# JammerCon_v1_1.net
KiCad netlist of a schematic drawn in Altium Designer
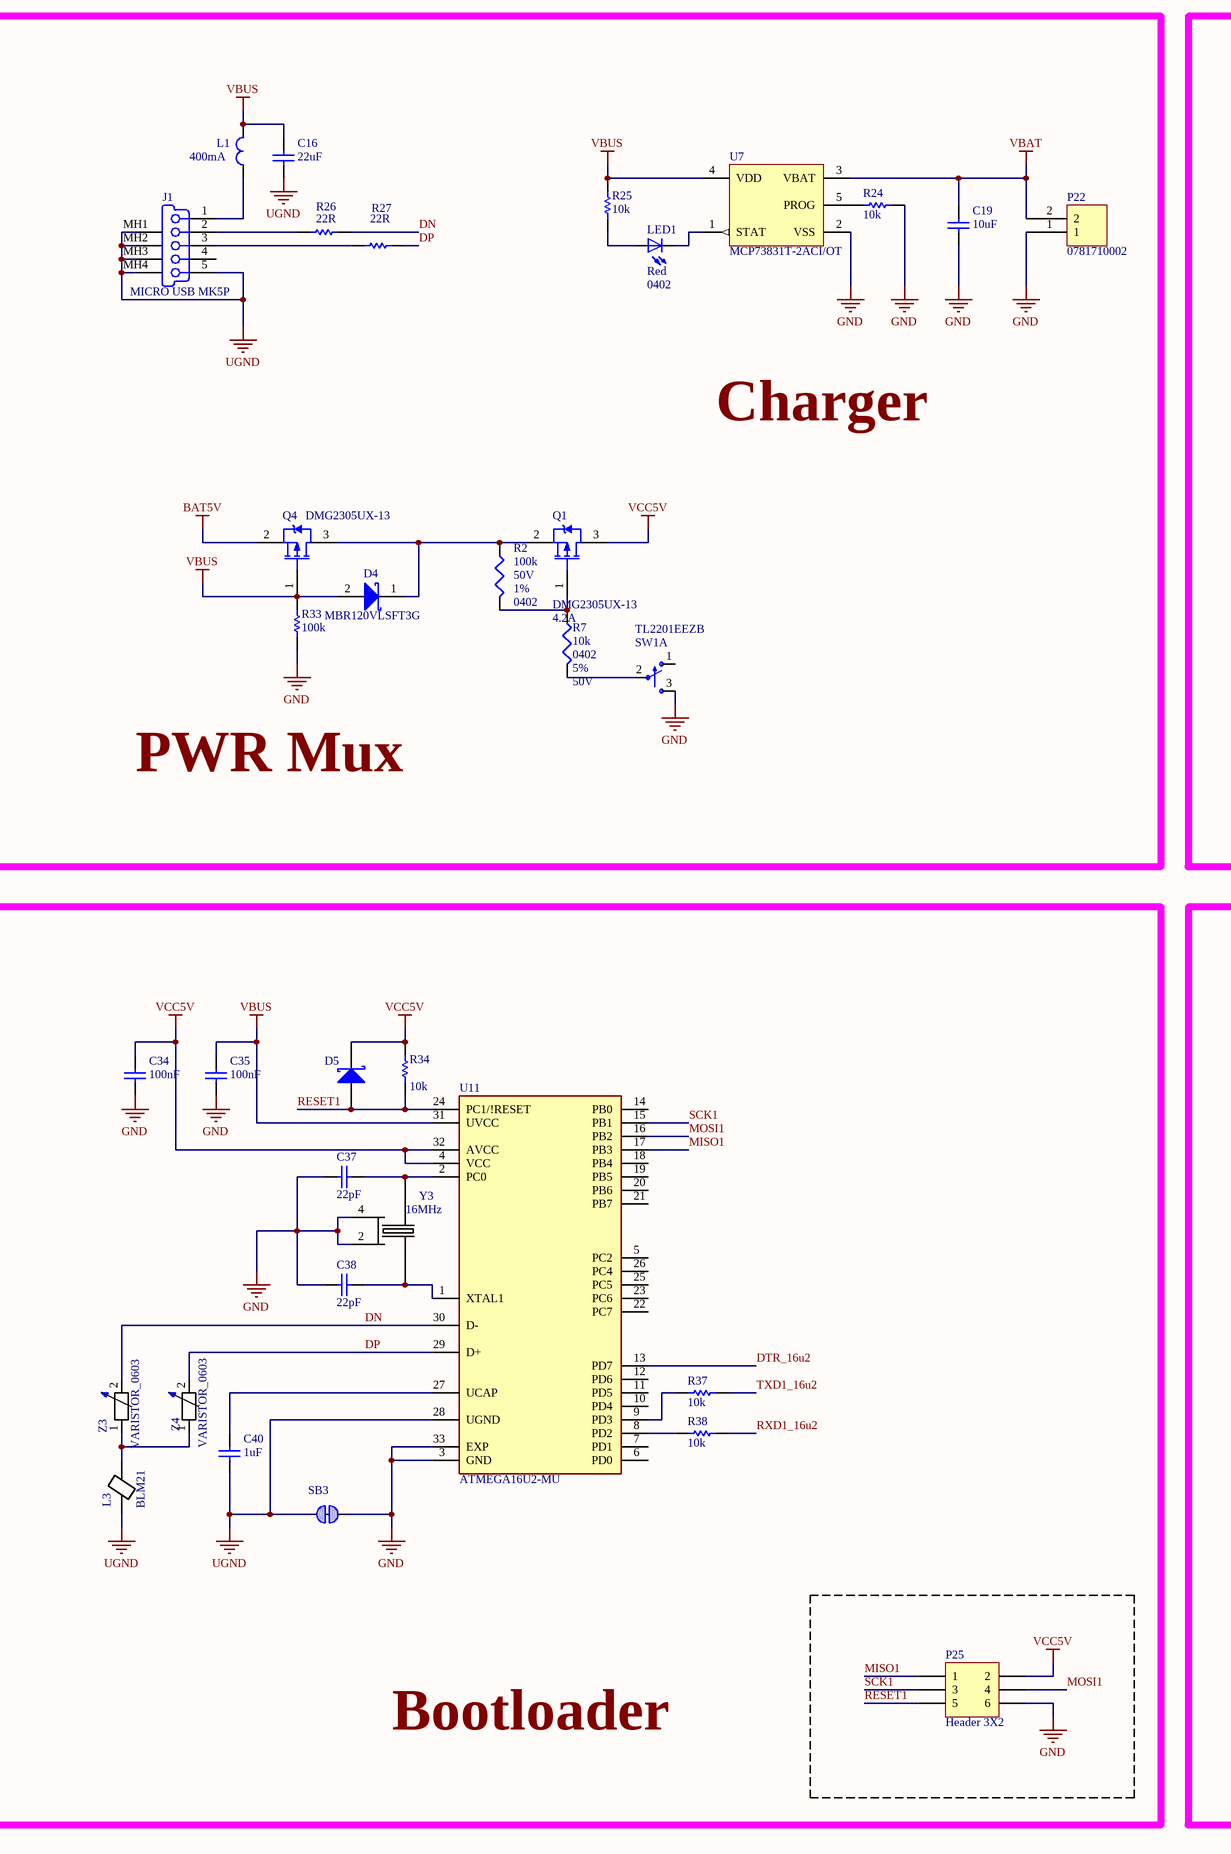
[diagram p0: JammerCon_v1.1.SchDoc, left]
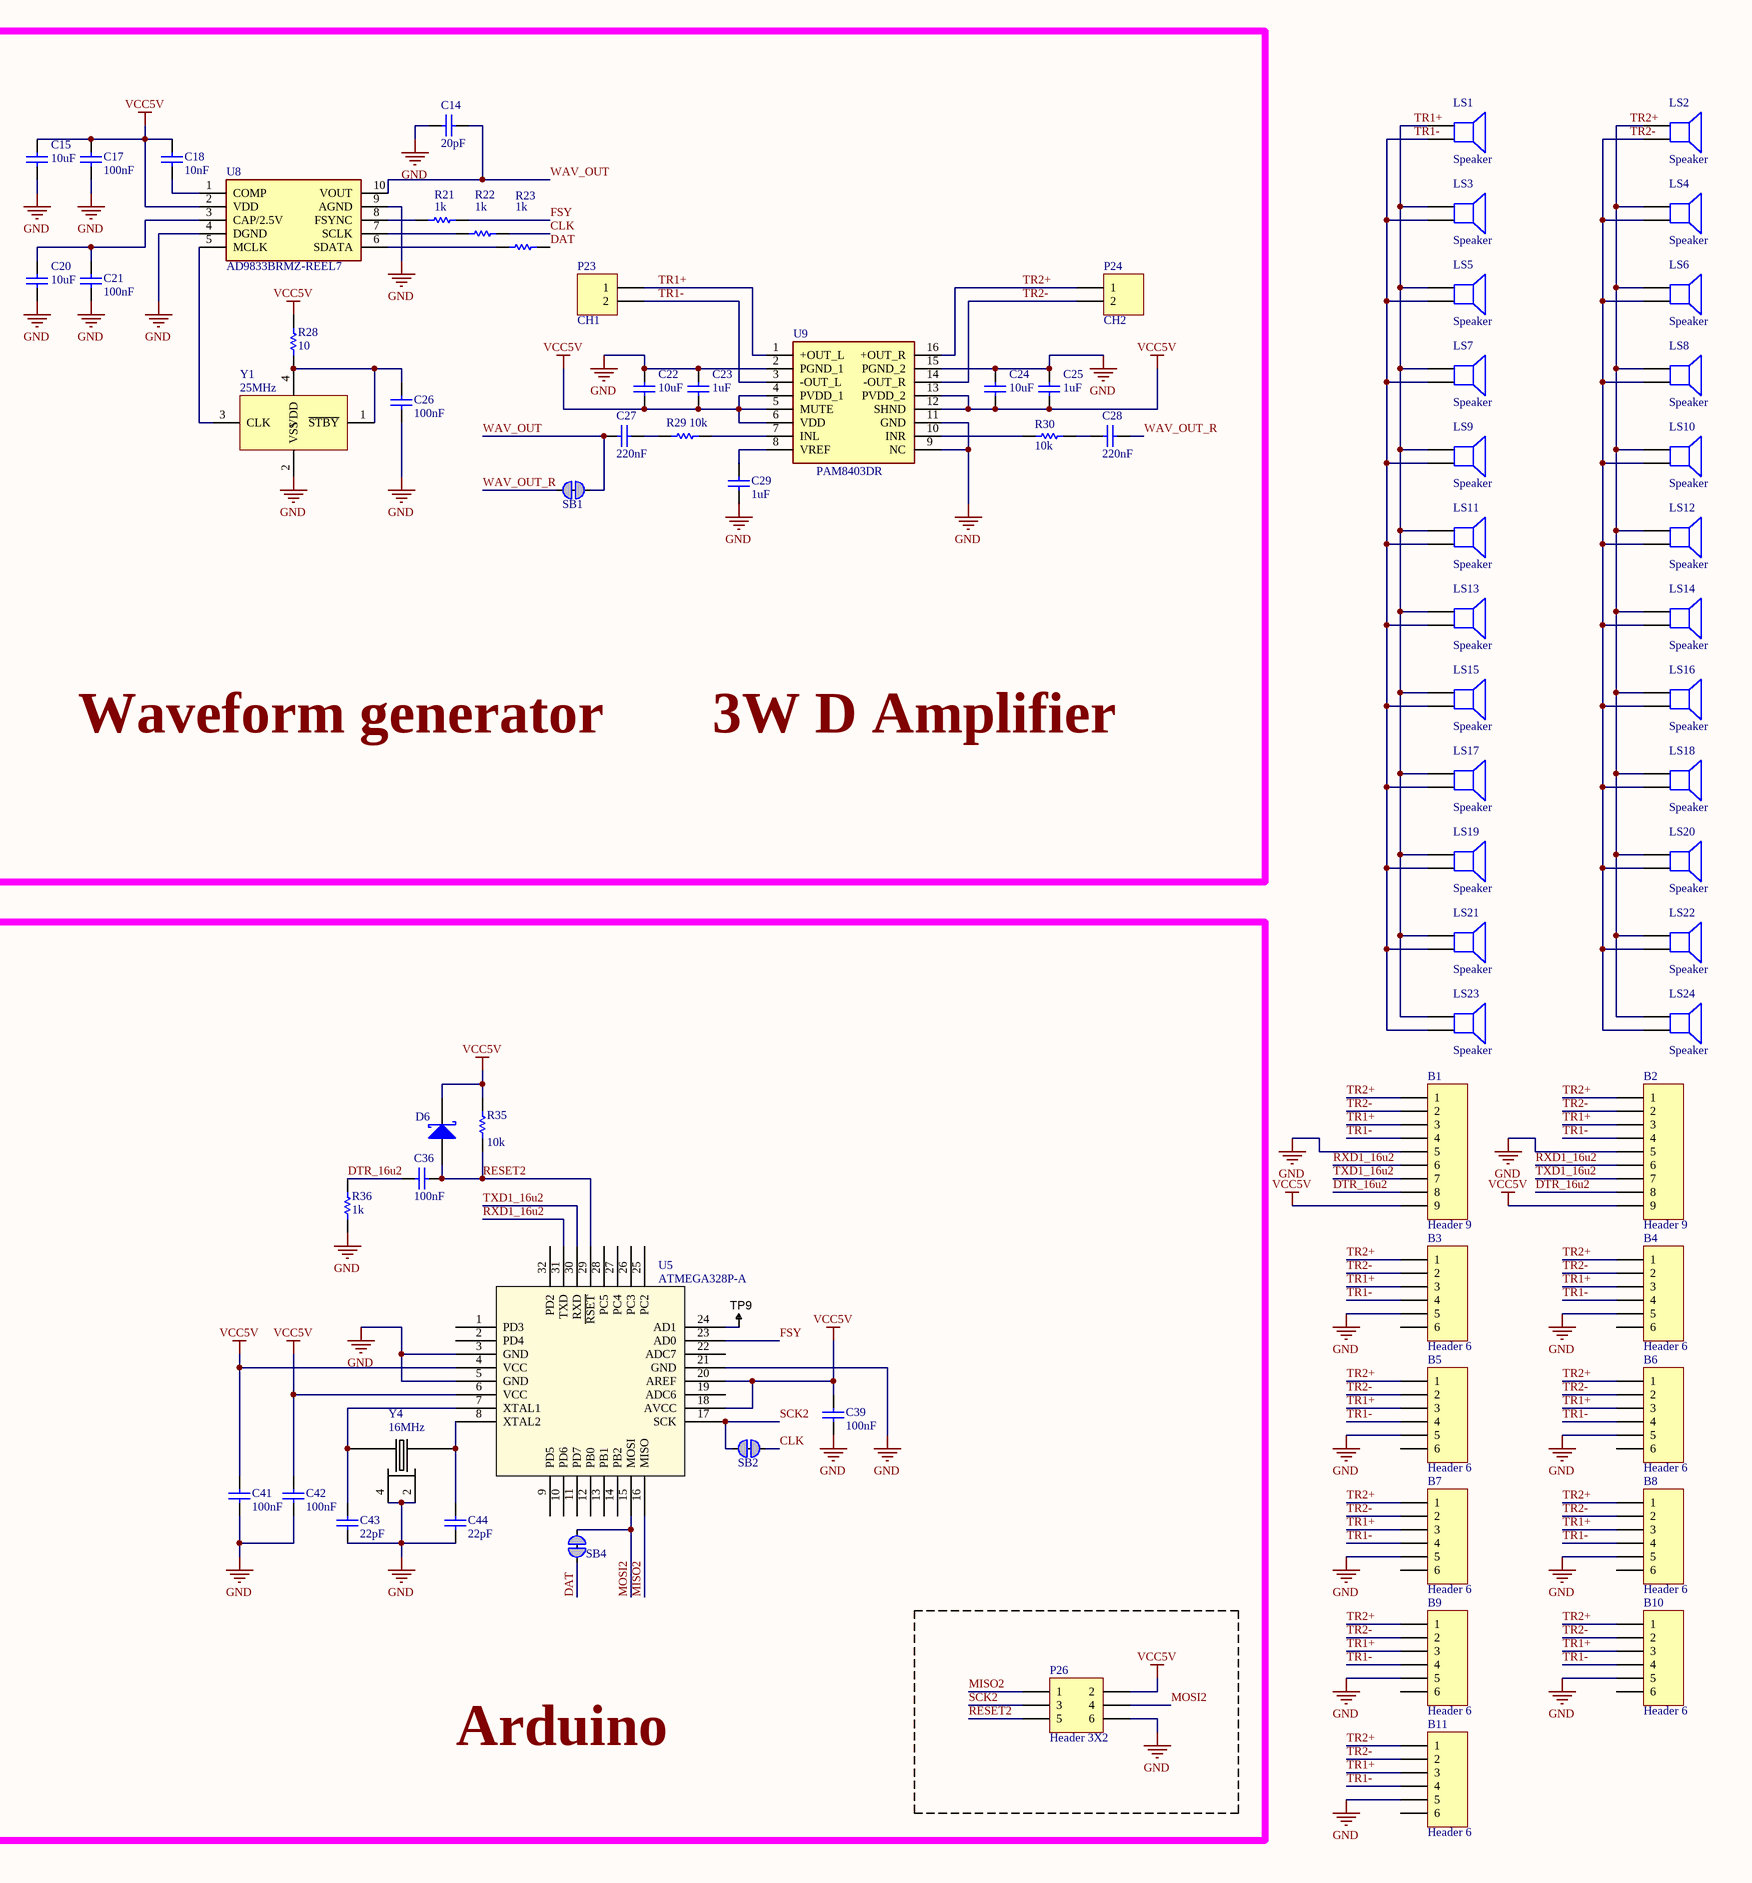
[diagram p1: JammerCon_v1.1.SchDoc, right]

(export (version "E")
  (design (tool "Eeschema 10.0.6"))
  (components
    (comp (ref "B1")
      (value "Header 9")
      (footprint "HDR1X9")
      (description "Header, 9-Pin")
      (fields (field (name "PUBLISHER") "Altium Limited"))
      (libsource (lib "Miscellaneous Connectors") (part "Header 9"))
    )
    (comp (ref "B2")
      (value "Header 9")
      (footprint "HDR1X9")
      (description "Header, 9-Pin")
      (fields (field (name "PUBLISHER") "Altium Limited"))
      (libsource (lib "Miscellaneous Connectors") (part "Header 9"))
    )
    (comp (ref "B3")
      (value "Header 6")
      (footprint "HDR1X6")
      (description "Header, 6-Pin")
      (fields (field (name "PUBLISHER") "Altium Limited"))
      (libsource (lib "Miscellaneous Connectors") (part "Header 6"))
    )
    (comp (ref "B4")
      (value "Header 6")
      (footprint "HDR1X6")
      (description "Header, 6-Pin")
      (fields (field (name "PUBLISHER") "Altium Limited"))
      (libsource (lib "Miscellaneous Connectors") (part "Header 6"))
    )
    (comp (ref "B5")
      (value "Header 6")
      (footprint "HDR1X6")
      (description "Header, 6-Pin")
      (fields (field (name "PUBLISHER") "Altium Limited"))
      (libsource (lib "Miscellaneous Connectors") (part "Header 6"))
    )
    (comp (ref "B6")
      (value "Header 6")
      (footprint "HDR1X6")
      (description "Header, 6-Pin")
      (fields (field (name "PUBLISHER") "Altium Limited"))
      (libsource (lib "Miscellaneous Connectors") (part "Header 6"))
    )
    (comp (ref "B7")
      (value "Header 6")
      (footprint "HDR1X6")
      (description "Header, 6-Pin")
      (fields (field (name "PUBLISHER") "Altium Limited"))
      (libsource (lib "Miscellaneous Connectors") (part "Header 6"))
    )
    (comp (ref "B8")
      (value "Header 6")
      (footprint "HDR1X6")
      (description "Header, 6-Pin")
      (fields (field (name "PUBLISHER") "Altium Limited"))
      (libsource (lib "Miscellaneous Connectors") (part "Header 6"))
    )
    (comp (ref "B9")
      (value "Header 6")
      (footprint "HDR1X6")
      (description "Header, 6-Pin")
      (fields (field (name "PUBLISHER") "Altium Limited"))
      (libsource (lib "Miscellaneous Connectors") (part "Header 6"))
    )
    (comp (ref "B10")
      (value "Header 6")
      (footprint "HDR1X6")
      (description "Header, 6-Pin")
      (fields (field (name "PUBLISHER") "Altium Limited"))
      (libsource (lib "Miscellaneous Connectors") (part "Header 6"))
    )
    (comp (ref "B11")
      (value "Header 6")
      (footprint "HDR1X6")
      (description "Header, 6-Pin")
      (fields (field (name "PUBLISHER") "Altium Limited"))
      (libsource (lib "Miscellaneous Connectors") (part "Header 6"))
    )
    (comp (ref "C14")
      (value "20pF")
      (footprint "C0402")
      (description "Capacitor (Semiconductor SIM Model)")
      (fields (field (name "Comment") "Cap Semi"))
      (libsource (lib "Miscellaneous Devices") (part "Cap Semi"))
    )
    (comp (ref "C15")
      (value "10uF")
      (footprint "C0805")
      (description "Capacitor (Semiconductor SIM Model)")
      (fields (field (name "Comment") "Cap Semi"))
      (libsource (lib "Miscellaneous Devices") (part "Cap Semi"))
    )
    (comp (ref "C16")
      (value "22uF")
      (footprint "C0603")
      (description "Capacitor (Semiconductor SIM Model)")
      (fields (field (name "Comment") "Cap Semi"))
      (libsource (lib "Miscellaneous Devices") (part "Cap Semi"))
    )
    (comp (ref "C17")
      (value "100nF")
      (footprint "R0402")
      (description "Capacitor (Semiconductor SIM Model)")
      (fields (field (name "Comment") "Cap Semi"))
      (libsource (lib "Miscellaneous Devices") (part "Cap Semi"))
    )
    (comp (ref "C18")
      (value "10nF")
      (footprint "R0402")
      (description "Capacitor (Semiconductor SIM Model)")
      (fields (field (name "Comment") "Cap Semi"))
      (libsource (lib "Miscellaneous Devices") (part "Cap Semi"))
    )
    (comp (ref "C19")
      (value "10uF")
      (footprint "C0402")
      (description "Capacitor (Semiconductor SIM Model)")
      (fields (field (name "Comment") "Cap Semi"))
      (libsource (lib "Miscellaneous Devices") (part "Cap Semi"))
    )
    (comp (ref "C20")
      (value "10uF")
      (footprint "C0805")
      (description "Capacitor (Semiconductor SIM Model)")
      (fields (field (name "Comment") "Cap Semi"))
      (libsource (lib "Miscellaneous Devices") (part "Cap Semi"))
    )
    (comp (ref "C21")
      (value "100nF")
      (footprint "R0402")
      (description "Capacitor (Semiconductor SIM Model)")
      (fields (field (name "Comment") "Cap Semi"))
      (libsource (lib "Miscellaneous Devices") (part "Cap Semi"))
    )
    (comp (ref "C22")
      (value "10uF")
      (footprint "C0603")
      (description "Capacitor (Semiconductor SIM Model)")
      (fields (field (name "Comment") "Cap Semi"))
      (libsource (lib "Miscellaneous Devices") (part "Cap Semi"))
    )
    (comp (ref "C23")
      (value "1uF")
      (footprint "C0603")
      (description "Capacitor (Semiconductor SIM Model)")
      (fields (field (name "Comment") "Cap Semi"))
      (libsource (lib "Miscellaneous Devices") (part "Cap Semi"))
    )
    (comp (ref "C24")
      (value "10uF")
      (footprint "C0603")
      (description "Capacitor (Semiconductor SIM Model)")
      (fields (field (name "Comment") "Cap Semi"))
      (libsource (lib "Miscellaneous Devices") (part "Cap Semi"))
    )
    (comp (ref "C25")
      (value "1uF")
      (footprint "C0603")
      (description "Capacitor (Semiconductor SIM Model)")
      (fields (field (name "Comment") "Cap Semi"))
      (libsource (lib "Miscellaneous Devices") (part "Cap Semi"))
    )
    (comp (ref "C26")
      (value "100nF")
      (footprint "R0402")
      (description "Capacitor (Semiconductor SIM Model)")
      (fields (field (name "Comment") "Cap Semi"))
      (libsource (lib "Miscellaneous Devices") (part "Cap Semi"))
    )
    (comp (ref "C27")
      (value "220nF")
      (footprint "C0603")
      (description "Capacitor (Semiconductor SIM Model)")
      (fields (field (name "Comment") "Cap Semi"))
      (libsource (lib "Miscellaneous Devices") (part "Cap Semi"))
    )
    (comp (ref "C28")
      (value "220nF")
      (footprint "C0603")
      (description "Capacitor (Semiconductor SIM Model)")
      (fields (field (name "Comment") "Cap Semi"))
      (libsource (lib "Miscellaneous Devices") (part "Cap Semi"))
    )
    (comp (ref "C29")
      (value "1uF")
      (footprint "R0402")
      (description "Capacitor (Semiconductor SIM Model)")
      (fields (field (name "Comment") "Cap Semi"))
      (libsource (lib "Miscellaneous Devices") (part "Cap Semi"))
    )
    (comp (ref "C34")
      (value "100nF")
      (footprint "C0201")
      (description "Capacitor (Semiconductor SIM Model)")
      (fields (field (name "Comment") "Cap Semi"))
      (libsource (lib "Miscellaneous Devices") (part "Cap Semi"))
    )
    (comp (ref "C35")
      (value "100nF")
      (footprint "C0201")
      (description "Capacitor (Semiconductor SIM Model)")
      (fields (field (name "Comment") "Cap Semi"))
      (libsource (lib "Miscellaneous Devices") (part "Cap Semi"))
    )
    (comp (ref "C36")
      (value "100nF")
      (footprint "R0402")
      (description "Capacitor (Semiconductor SIM Model)")
      (fields (field (name "Comment") "Cap Semi"))
      (libsource (lib "Miscellaneous Devices") (part "Cap Semi"))
    )
    (comp (ref "C37")
      (value "22pF")
      (footprint "C0402")
      (description "Capacitor (Semiconductor SIM Model)")
      (fields (field (name "Comment") "Cap Semi"))
      (libsource (lib "Miscellaneous Devices") (part "Cap Semi"))
    )
    (comp (ref "C38")
      (value "22pF")
      (footprint "C0402")
      (description "Capacitor (Semiconductor SIM Model)")
      (fields (field (name "Comment") "Cap Semi"))
      (libsource (lib "Miscellaneous Devices") (part "Cap Semi"))
    )
    (comp (ref "C39")
      (value "100nF")
      (footprint "R0402")
      (description "Capacitor (Semiconductor SIM Model)")
      (fields (field (name "Comment") "Cap Semi"))
      (libsource (lib "Miscellaneous Devices") (part "Cap Semi"))
    )
    (comp (ref "C40")
      (value "1uF")
      (footprint "C0402")
      (description "Capacitor (Semiconductor SIM Model)")
      (fields (field (name "Comment") "Cap Semi"))
      (libsource (lib "Miscellaneous Devices") (part "Cap Semi"))
    )
    (comp (ref "C41")
      (value "100nF")
      (footprint "R0402")
      (description "Capacitor (Semiconductor SIM Model)")
      (fields (field (name "Comment") "Cap Semi"))
      (libsource (lib "Miscellaneous Devices") (part "Cap Semi"))
    )
    (comp (ref "C42")
      (value "100nF")
      (footprint "R0402")
      (description "Capacitor (Semiconductor SIM Model)")
      (fields (field (name "Comment") "Cap Semi"))
      (libsource (lib "Miscellaneous Devices") (part "Cap Semi"))
    )
    (comp (ref "C43")
      (value "22pF")
      (footprint "C0402")
      (description "Capacitor (Semiconductor SIM Model)")
      (fields (field (name "Comment") "Cap Semi"))
      (libsource (lib "Miscellaneous Devices") (part "Cap Semi"))
    )
    (comp (ref "C44")
      (value "22pF")
      (footprint "C0402")
      (description "Capacitor (Semiconductor SIM Model)")
      (fields (field (name "Comment") "Cap Semi"))
      (libsource (lib "Miscellaneous Devices") (part "Cap Semi"))
    )
    (comp (ref "D4")
      (value "MBR120VLSFT3G")
      (footprint "SOD-123FL")
      (description "Schottky Diodes & Rectifiers 1A 20V")
      (fields (field (name "MANUFACTURER") "ON Semiconductor"))
      (libsource (lib "Miscellaneous Devices") (part "D Schottky"))
    )
    (comp (ref "D5")
      (value "ZENER 5.6V")
      (footprint "SOD-323")
      (description "Zener Diode 5.6V SOD-323F")
      (fields
        (field (name "MANUFACTURER") "ON Semiconductor / Fairchild")
        (field (name "MANUFACTURER PART NUMBER") "MM3Z5V6B")
      )
      (libsource (lib "Miscellaneous Devices") (part "Diode 18TQ045"))
    )
    (comp (ref "D6")
      (value "ZENER 5.6V")
      (footprint "SOD-323")
      (description "Zener Diode 5.6V SOD-323F")
      (fields
        (field (name "MANUFACTURER") "ON Semiconductor / Fairchild")
        (field (name "MANUFACTURER PART NUMBER") "MM3Z5V6B")
      )
      (libsource (lib "Miscellaneous Devices") (part "Diode 18TQ045"))
    )
    (comp (ref "J1")
      (value "MICRO USB MK5P")
      (footprint "1050170001")
      (description "USB On-The-Go (OTG) Mini-B")
      (libsource (lib "jamming_1") (part "USB_Mini_B"))
    )
    (comp (ref "L1")
      (value "BMB2A0430RS2")
      (footprint "L0603")
      (description "FERRITE BEAD INDUCTOR")
      (fields
        (field (name "MANUFACTURER") "Taiyo Yuden")
        (field (name "MANUFACTURER PART NUMBER") "BK1608HW431-T")
        (field (name "MAX DC CURRENT") "400mA")
      )
      (libsource (lib "ELEX") (part "BEAD"))
    )
    (comp (ref "L3")
      (value "BLM21")
      (footprint "*BEADC2012X87N")
      (description "Ferrite Beads Multi-Layer 330Ohm 25% 100MHz 1.5A 70mOhm DCR 0805 Paper T/R")
      (fields (field (name "MP") "BLM21PG331SN1D") (field (name "MF") "Murata"))
      (libsource (lib "Component_1") (part "BLM21PG331SN1D"))
    )
    (comp (ref "LED1")
      (value "~")
      (footprint "LED-0402-RED")
      (description "Red LED 0402")
      (fields
        (field (name "MANUFACTURER") "SunLED")
        (field (name "MANUFACTURER PART NUMBER") "XZMDK68W-2")
        (field (name "COLOR") "Red")
        (field (name "CASE/PACKAGE") "0402")
      )
      (libsource (lib "jamming") (part "LED0402 red"))
    )
    (comp (ref "LS1")
      (value "Speaker")
      (footprint "ULTRASONICSENSOR")
      (description "Loudspeaker")
      (libsource (lib "Miscellaneous Devices") (part "Speaker"))
    )
    (comp (ref "LS2")
      (value "Speaker")
      (footprint "ULTRASONICSENSOR")
      (description "Loudspeaker")
      (fields (field (name "PUBLISHER") "Altium Limited"))
      (libsource (lib "Miscellaneous Devices") (part "Speaker"))
    )
    (comp (ref "LS3")
      (value "Speaker")
      (footprint "ULTRASONICSENSOR")
      (description "Loudspeaker")
      (fields (field (name "PUBLISHER") "Altium Limited"))
      (libsource (lib "Miscellaneous Devices") (part "Speaker"))
    )
    (comp (ref "LS4")
      (value "Speaker")
      (footprint "ULTRASONICSENSOR")
      (description "Loudspeaker")
      (fields (field (name "PUBLISHER") "Altium Limited"))
      (libsource (lib "Miscellaneous Devices") (part "Speaker"))
    )
    (comp (ref "LS5")
      (value "Speaker")
      (footprint "ULTRASONICSENSOR")
      (description "Loudspeaker")
      (fields (field (name "PUBLISHER") "Altium Limited"))
      (libsource (lib "Miscellaneous Devices") (part "Speaker"))
    )
    (comp (ref "LS6")
      (value "Speaker")
      (footprint "ULTRASONICSENSOR")
      (description "Loudspeaker")
      (fields (field (name "PUBLISHER") "Altium Limited"))
      (libsource (lib "Miscellaneous Devices") (part "Speaker"))
    )
    (comp (ref "LS7")
      (value "Speaker")
      (footprint "ULTRASONICSENSOR")
      (description "Loudspeaker")
      (fields (field (name "PUBLISHER") "Altium Limited"))
      (libsource (lib "Miscellaneous Devices") (part "Speaker"))
    )
    (comp (ref "LS8")
      (value "Speaker")
      (footprint "ULTRASONICSENSOR")
      (description "Loudspeaker")
      (fields (field (name "PUBLISHER") "Altium Limited"))
      (libsource (lib "Miscellaneous Devices") (part "Speaker"))
    )
    (comp (ref "LS9")
      (value "Speaker")
      (footprint "ULTRASONICSENSOR")
      (description "Loudspeaker")
      (fields (field (name "PUBLISHER") "Altium Limited"))
      (libsource (lib "Miscellaneous Devices") (part "Speaker"))
    )
    (comp (ref "LS10")
      (value "Speaker")
      (footprint "ULTRASONICSENSOR")
      (description "Loudspeaker")
      (fields (field (name "PUBLISHER") "Altium Limited"))
      (libsource (lib "Miscellaneous Devices") (part "Speaker"))
    )
    (comp (ref "LS11")
      (value "Speaker")
      (footprint "ULTRASONICSENSOR")
      (description "Loudspeaker")
      (fields (field (name "PUBLISHER") "Altium Limited"))
      (libsource (lib "Miscellaneous Devices") (part "Speaker"))
    )
    (comp (ref "LS12")
      (value "Speaker")
      (footprint "ULTRASONICSENSOR")
      (description "Loudspeaker")
      (fields (field (name "PUBLISHER") "Altium Limited"))
      (libsource (lib "Miscellaneous Devices") (part "Speaker"))
    )
    (comp (ref "LS13")
      (value "Speaker")
      (footprint "ULTRASONICSENSOR")
      (description "Loudspeaker")
      (fields (field (name "PUBLISHER") "Altium Limited"))
      (libsource (lib "Miscellaneous Devices") (part "Speaker"))
    )
    (comp (ref "LS14")
      (value "Speaker")
      (footprint "ULTRASONICSENSOR")
      (description "Loudspeaker")
      (fields (field (name "PUBLISHER") "Altium Limited"))
      (libsource (lib "Miscellaneous Devices") (part "Speaker"))
    )
    (comp (ref "LS15")
      (value "Speaker")
      (footprint "ULTRASONICSENSOR")
      (description "Loudspeaker")
      (fields (field (name "PUBLISHER") "Altium Limited"))
      (libsource (lib "Miscellaneous Devices") (part "Speaker"))
    )
    (comp (ref "LS16")
      (value "Speaker")
      (footprint "ULTRASONICSENSOR")
      (description "Loudspeaker")
      (fields (field (name "PUBLISHER") "Altium Limited"))
      (libsource (lib "Miscellaneous Devices") (part "Speaker"))
    )
    (comp (ref "LS17")
      (value "Speaker")
      (footprint "ULTRASONICSENSOR")
      (description "Loudspeaker")
      (fields (field (name "PUBLISHER") "Altium Limited"))
      (libsource (lib "Miscellaneous Devices") (part "Speaker"))
    )
    (comp (ref "LS18")
      (value "Speaker")
      (footprint "ULTRASONICSENSOR")
      (description "Loudspeaker")
      (fields (field (name "PUBLISHER") "Altium Limited"))
      (libsource (lib "Miscellaneous Devices") (part "Speaker"))
    )
    (comp (ref "LS19")
      (value "Speaker")
      (footprint "ULTRASONICSENSOR")
      (description "Loudspeaker")
      (fields (field (name "PUBLISHER") "Altium Limited"))
      (libsource (lib "Miscellaneous Devices") (part "Speaker"))
    )
    (comp (ref "LS20")
      (value "Speaker")
      (footprint "ULTRASONICSENSOR")
      (description "Loudspeaker")
      (fields (field (name "PUBLISHER") "Altium Limited"))
      (libsource (lib "Miscellaneous Devices") (part "Speaker"))
    )
    (comp (ref "LS21")
      (value "Speaker")
      (footprint "ULTRASONICSENSOR")
      (description "Loudspeaker")
      (fields (field (name "PUBLISHER") "Altium Limited"))
      (libsource (lib "Miscellaneous Devices") (part "Speaker"))
    )
    (comp (ref "LS22")
      (value "Speaker")
      (footprint "ULTRASONICSENSOR")
      (description "Loudspeaker")
      (fields (field (name "PUBLISHER") "Altium Limited"))
      (libsource (lib "Miscellaneous Devices") (part "Speaker"))
    )
    (comp (ref "LS23")
      (value "Speaker")
      (footprint "ULTRASONICSENSOR")
      (description "Loudspeaker")
      (fields (field (name "PUBLISHER") "Altium Limited"))
      (libsource (lib "Miscellaneous Devices") (part "Speaker"))
    )
    (comp (ref "LS24")
      (value "Speaker")
      (footprint "ULTRASONICSENSOR")
      (description "Loudspeaker")
      (fields (field (name "PUBLISHER") "Altium Limited"))
      (libsource (lib "Miscellaneous Devices") (part "Speaker"))
    )
    (comp (ref "P22")
      (value "SMT Battery connector")
      (footprint "CONN_MOLEX_781710002")
      (description "1.20MM WTB HEADER VERT 2POS")
      (fields (field (name "MANUFACTURER") "Molex") (field (name "MANUFACTURER PART NUMBER") "0781710002"))
      (libsource (lib "jamming_1") (part "CONN_MOLEX_0781710002"))
    )
    (comp (ref "P23")
      (value "CH1")
      (footprint "HDR1X2")
      (description "Header, 2-Pin")
      (fields (field (name "PUBLISHER") "Altium Limited"))
      (libsource (lib "Miscellaneous Connectors") (part "Header 2"))
    )
    (comp (ref "P24")
      (value "CH2")
      (footprint "HDR1X2")
      (description "Header, 2-Pin")
      (fields (field (name "PUBLISHER") "Altium Limited"))
      (libsource (lib "") (part "Header 2_1"))
    )
    (comp (ref "P25")
      (value "Header 3X2")
      (footprint "TC2030-MCP")
      (description "Header, 3-Pin, Dual row")
      (libsource (lib "Miscellaneous Connectors") (part "Header 3X2"))
    )
    (comp (ref "P26")
      (value "Header 3X2")
      (footprint "TC2030-MCP")
      (description "Header, 3-Pin, Dual row")
      (libsource (lib "Miscellaneous Connectors") (part "Header 3X2"))
    )
    (comp (ref "Q1")
      (value "DMG2305UX-13")
      (footprint "SOT23-3")
      (description "MOSFET P-CH 20V 4.2A SOT23")
      (fields (field (name "MANUFACTURER") "Diodes") (field (name "CONTINUOUS DRAIN CURRENT (ID)") "4.2A"))
      (libsource (lib "Symbols") (part "ZXMP10A13FTA"))
    )
    (comp (ref "Q4")
      (value "~")
      (footprint "SOT23-3")
      (description "MOSFET P-CH 20V 4.2A SOT23")
      (fields (field (name "MANUFACTURER") "Diodes") (field (name "MANUFACTURER PART NUMBER") "DMG2305UX-13"))
      (libsource (lib "jamming_1") (part "DMG2305UX-13"))
    )
    (comp (ref "R2")
      (value "100k")
      (footprint "R0402")
      (description "Resistor")
      (fields
        (field (name "MANUFACTURER") "Yageo")
        (field (name "MANUFACTURER PART NUMBER") "RC0402FR-07100KL")
        (field (name "CASE/PACKAGE") "0402")
        (field (name "TOLERANCE") "1%")
        (field (name "VOLTAGE RATING") "50V")
      )
      (libsource (lib "Miscellaneous Devices") (part "Res3"))
    )
    (comp (ref "R7")
      (value "10k")
      (footprint "R0402")
      (description "Resistor")
      (fields
        (field (name "MANUFACTURER") "TE Connectivity")
        (field (name "MANUFACTURER PART NUMBER") "CRG0402J10K/10")
        (field (name "CASE/PACKAGE") "0402")
        (field (name "TOLERANCE") "5%")
        (field (name "VOLTAGE RATING") "50V")
      )
      (libsource (lib "Miscellaneous Devices") (part "Res3"))
    )
    (comp (ref "R21")
      (value "1k")
      (footprint "R0402")
      (description "Semiconductor Resistor")
      (fields (field (name "Comment") "Res0402"))
      (libsource (lib "jamming") (part "Res0402"))
    )
    (comp (ref "R22")
      (value "1k")
      (footprint "R0402")
      (description "Semiconductor Resistor")
      (fields (field (name "Comment") "Res0402"))
      (libsource (lib "jamming") (part "Res0402"))
    )
    (comp (ref "R23")
      (value "1k")
      (footprint "R0402")
      (description "Semiconductor Resistor")
      (fields (field (name "Comment") "Res0402"))
      (libsource (lib "jamming") (part "Res0402"))
    )
    (comp (ref "R24")
      (value "10k")
      (footprint "R0402")
      (description "Semiconductor Resistor")
      (fields (field (name "Comment") "Res0402"))
      (libsource (lib "jamming") (part "Res0201"))
    )
    (comp (ref "R25")
      (value "10k")
      (footprint "R0402")
      (description "Semiconductor Resistor")
      (fields (field (name "Comment") "Res0402"))
      (libsource (lib "jamming") (part "Res0201"))
    )
    (comp (ref "R26")
      (value "22R")
      (footprint "R0402")
      (description "Semiconductor Resistor")
      (fields (field (name "Comment") "Res0402"))
      (libsource (lib "jamming") (part "Res0402"))
    )
    (comp (ref "R27")
      (value "22R")
      (footprint "R0402")
      (description "Semiconductor Resistor")
      (fields (field (name "Comment") "Res0402"))
      (libsource (lib "jamming") (part "Res0402"))
    )
    (comp (ref "R28")
      (value "10")
      (footprint "R0402")
      (description "Semiconductor Resistor")
      (fields (field (name "Comment") "Res0402"))
      (libsource (lib "jamming") (part "Res0402"))
    )
    (comp (ref "R29")
      (value "10k")
      (footprint "R0603")
      (description "Semiconductor Resistor")
      (fields (field (name "Comment") "Res0402"))
      (libsource (lib "jamming") (part "Res0402"))
    )
    (comp (ref "R30")
      (value "10k")
      (footprint "R0603")
      (description "Semiconductor Resistor")
      (fields (field (name "Comment") "Res0402"))
      (libsource (lib "jamming") (part "Res0402"))
    )
    (comp (ref "R33")
      (value "100k")
      (footprint "R0402")
      (description "Semiconductor Resistor")
      (fields (field (name "Comment") "Res0402"))
      (libsource (lib "jamming") (part "Res0201"))
    )
    (comp (ref "R34")
      (value "10k")
      (footprint "R0402")
      (description "Semiconductor Resistor")
      (fields (field (name "Comment") "Res0402"))
      (libsource (lib "jamming") (part "Res0402"))
    )
    (comp (ref "R35")
      (value "10k")
      (footprint "R0402")
      (description "Semiconductor Resistor")
      (fields (field (name "Comment") "Res0402"))
      (libsource (lib "jamming") (part "Res0402"))
    )
    (comp (ref "R36")
      (value "1k")
      (footprint "R0402")
      (description "Semiconductor Resistor")
      (fields (field (name "Comment") "Res"))
      (libsource (lib "jamming") (part "Res0201"))
    )
    (comp (ref "R37")
      (value "10k")
      (footprint "R0201")
      (description "Semiconductor Resistor")
      (fields (field (name "Comment") "Res0201"))
      (libsource (lib "jamming") (part "Res0201"))
    )
    (comp (ref "R38")
      (value "10k")
      (footprint "R0201")
      (description "Semiconductor Resistor")
      (fields (field (name "Comment") "Res0201"))
      (libsource (lib "jamming") (part "Res0201"))
    )
    (comp (ref "SB1")
      (value "Solderbridge")
      (footprint "Solderbridge_Shorted")
      (description "Shorted Solderbridge")
      (libsource (lib "Component_1") (part "SOLDERBRIDGE_SHORTED"))
    )
    (comp (ref "SB2")
      (value "Solderbridge")
      (footprint "Solderbridge_Shorted")
      (description "Shorted Solderbridge")
      (libsource (lib "Component_1") (part "SOLDERBRIDGE_SHORTED"))
    )
    (comp (ref "SB3")
      (value "Solderbridge")
      (footprint "Solderbridge_Shorted")
      (description "Shorted Solderbridge")
      (libsource (lib "Component_1") (part "SOLDERBRIDGE_SHORTED"))
    )
    (comp (ref "SB4")
      (value "Solderbridge")
      (footprint "Solderbridge_Shorted")
      (description "Shorted Solderbridge")
      (libsource (lib "Component_1") (part "SOLDERBRIDGE_SHORTED"))
    )
    (comp (ref "SW1")
      (value "TL2201EEZB")
      (footprint "TL2201EEZB")
      (description "Pushbutton Switch DPDT Standard Through Hole")
      (fields (field (name "MF") "E-Switch"))
      (libsource (lib "Component_1") (part "TL2201EEZB"))
    )
    (comp (ref "TP9")
      (value "TESTPOINT")
      (footprint "TP-R60")
      (description "SMD test pin")
      (libsource (lib "PBL - Test Points") (part "TESTPOINT"))
    )
    (comp (ref "U5")
      (value "ATMEGA328P-A")
      (footprint "ATMEGA328P")
      (description "IC, SWITCH, SPDT ANA, SMD")
      (fields
        (field (name "MANUFACTURER") "Microchip / Atmel")
        (field (name "MANUFACTURER PART NUMBER") "ATMEGA328PB-AUR")
      )
      (libsource (lib "Component_1") (part "ATMEGA328P-A"))
    )
    (comp (ref "U7")
      (value "MCP73831T-2ACI/OT")
      (footprint "SOT23-5")
      (description "IC CONTROLLR LI-ION 4.2V SOT23-5")
      (fields (field (name "MANUFACTURER") "Microchip Technology"))
      (libsource (lib "jamming_1") (part "MCP73831T-2ACI/OT_1"))
    )
    (comp (ref "U8")
      (value "AD9833BRMZ-REEL7")
      (footprint "SOP50P490X110-10N")
      (description "Integrated Circuit")
      (fields (field (name "MOUSER PART NUMBER") "584-AD9833BRMZ-R7"))
      (libsource (lib "jamming_1") (part "AD9833BRMZ-REEL7"))
    )
    (comp (ref "U9")
      (value "PAM8403DR")
      (footprint "SOIC127P605X175-16N")
      (description "Fuse")
      (libsource (lib "jamming") (part "PAM8403DR"))
    )
    (comp (ref "U11")
      (value "ATMEGA16U2-MU")
      (footprint "*QFN50P500X500X100-33N")
      (description "Integrated Circuit")
      (fields (field (name "MOUSER PART NUMBER") "556-ATMEGA16U2-MU"))
      (libsource (lib "jamming") (part "ATMEGA16U2-MU"))
    )
    (comp (ref "Y1")
      (value "25MHz")
      (footprint "OSC_ECS-3951M-250-BN-TR")
      (description "XTAL OSC XO 25.0000MHZ CMOS SMD")
      (fields
        (field (name "MANUFACTURER") "ECS International")
        (field (name "MANUFACTURER PART NUMBER") "ECS-3951M-250-BN-TR")
      )
      (libsource (lib "Component_1") (part "ECS-3951M-250-BN-TR"))
    )
    (comp (ref "Y3")
      (value "16MHz")
      (footprint "BT-XTAL_2016_N")
      (description "Crystal 32MHz")
      (libsource (lib "jamming") (part "416F32022CKR"))
    )
    (comp (ref "Y4")
      (value "16MHz")
      (footprint "BT-XTAL_2016_N")
      (description "Crystal 32MHz")
      (libsource (lib "jamming") (part "416F32022CKR"))
    )
    (comp (ref "Z3")
      (value "VARISTOR_0603")
      (footprint "*R0603")
      (description "Varistor, ESD Clamp Protector, 5 VDC, 20 Vclamp, IEC 61000-4-2 Level 4, 0603 SMD")
      (fields (field (name "MP") "CG0603MLC-05E") (field (name "MF") "Bourns"))
      (libsource (lib "Component_1") (part "SMD-RES-VARISTOR-5V-28V(0603)"))
    )
    (comp (ref "Z4")
      (value "VARISTOR_0603")
      (footprint "*R0603")
      (description "Varistor, ESD Clamp Protector, 5 VDC, 20 Vclamp, IEC 61000-4-2 Level 4, 0603 SMD")
      (fields (field (name "MP") "CG0603MLC-05E") (field (name "MF") "Bourns"))
      (libsource (lib "Component_1") (part "SMD-RES-VARISTOR-5V-28V(0603)"))
    )
  )
  (nets
    (net (code "1") (name "/CLK") (class "Default")
      (node (ref "R22") (pin "1") (pinfunction "1_1") (pintype "passive"))
      (node (ref "SB2") (pin "2") (pinfunction "1_2") (pintype "passive"))
    )
    (net (code "2") (name "/DAT") (class "Default")
      (node (ref "R23") (pin "1") (pinfunction "1_1") (pintype "passive"))
      (node (ref "SB4") (pin "2") (pinfunction "1_2") (pintype "passive"))
    )
    (net (code "3") (name "/DN") (class "Default")
      (node (ref "R26") (pin "1") (pinfunction "1_1") (pintype "passive"))
      (node (ref "U11") (pin "30") (pinfunction "D-_30") (pintype "passive"))
      (node (ref "Z3") (pin "2") (pinfunction "2_2") (pintype "passive"))
    )
    (net (code "4") (name "/DP") (class "Default")
      (node (ref "R27") (pin "1") (pinfunction "1_1") (pintype "passive"))
      (node (ref "U11") (pin "29") (pinfunction "D+_29") (pintype "passive"))
      (node (ref "Z4") (pin "2") (pinfunction "2_2") (pintype "passive"))
    )
    (net (code "5") (name "/DTR_16u2") (class "Default")
      (node (ref "B1") (pin "8") (pinfunction "8_8") (pintype "passive"))
      (node (ref "B2") (pin "8") (pinfunction "8_8") (pintype "passive"))
      (node (ref "C36") (pin "2") (pinfunction "2_2") (pintype "passive"))
      (node (ref "R36") (pin "2") (pinfunction "2_2") (pintype "passive"))
      (node (ref "U11") (pin "13") (pinfunction "PD7_13") (pintype "passive"))
    )
    (net (code "6") (name "/FSY") (class "Default")
      (node (ref "R21") (pin "1") (pinfunction "1_1") (pintype "passive"))
      (node (ref "U5") (pin "23") (pinfunction "AD0_23") (pintype "passive"))
    )
    (net (code "7") (name "/MISO1") (class "Default")
      (node (ref "P25") (pin "1") (pinfunction "1_1") (pintype "passive"))
      (node (ref "U11") (pin "17") (pinfunction "PB3_17") (pintype "passive"))
    )
    (net (code "8") (name "/MISO2") (class "Default")
      (node (ref "P26") (pin "1") (pinfunction "1_1") (pintype "passive"))
      (node (ref "U5") (pin "16") (pinfunction "MISO_16") (pintype "passive"))
    )
    (net (code "9") (name "/MOSI1") (class "Default")
      (node (ref "P25") (pin "4") (pinfunction "4_4") (pintype "passive"))
      (node (ref "U11") (pin "16") (pinfunction "PB2_16") (pintype "passive"))
    )
    (net (code "10") (name "/MOSI2") (class "Default")
      (node (ref "P26") (pin "4") (pinfunction "4_4") (pintype "passive"))
      (node (ref "SB4") (pin "1") (pinfunction "0_1") (pintype "passive"))
      (node (ref "U5") (pin "15") (pinfunction "MOSI_15") (pintype "passive"))
    )
    (net (code "11") (name "/RESET1") (class "Default")
      (node (ref "D5") (pin "1") (pinfunction "A_1") (pintype "passive"))
      (node (ref "P25") (pin "5") (pinfunction "5_5") (pintype "passive"))
      (node (ref "R34") (pin "1") (pinfunction "1_1") (pintype "passive"))
      (node (ref "U11") (pin "24") (pinfunction "PC1/!RESET_24") (pintype "passive"))
    )
    (net (code "12") (name "/RESET2") (class "Default")
      (node (ref "C36") (pin "1") (pinfunction "1_1") (pintype "passive"))
      (node (ref "D6") (pin "1") (pinfunction "A_1") (pintype "passive"))
      (node (ref "P26") (pin "5") (pinfunction "5_5") (pintype "passive"))
      (node (ref "R35") (pin "1") (pinfunction "1_1") (pintype "passive"))
      (node (ref "U5") (pin "29") (pinfunction "~{RSET}_29") (pintype "passive"))
    )
    (net (code "13") (name "/RXD1_16u2") (class "Default")
      (node (ref "B1") (pin "6") (pinfunction "6_6") (pintype "passive"))
      (node (ref "B2") (pin "6") (pinfunction "6_6") (pintype "passive"))
      (node (ref "R38") (pin "2") (pinfunction "2_2") (pintype "passive"))
      (node (ref "U5") (pin "31") (pinfunction "TXD_31") (pintype "passive"))
    )
    (net (code "14") (name "/SCK1") (class "Default")
      (node (ref "P25") (pin "3") (pinfunction "3_3") (pintype "passive"))
      (node (ref "U11") (pin "15") (pinfunction "PB1_15") (pintype "passive"))
    )
    (net (code "15") (name "/SCK2") (class "Default")
      (node (ref "P26") (pin "3") (pinfunction "3_3") (pintype "passive"))
      (node (ref "SB2") (pin "1") (pinfunction "0_1") (pintype "passive"))
      (node (ref "U5") (pin "17") (pinfunction "SCK_17") (pintype "passive"))
    )
    (net (code "16") (name "/TR1+") (class "Default")
      (node (ref "B1") (pin "3") (pinfunction "3_3") (pintype "passive"))
      (node (ref "B10") (pin "3") (pinfunction "3_3") (pintype "passive"))
      (node (ref "B11") (pin "3") (pinfunction "3_3") (pintype "passive"))
      (node (ref "B2") (pin "3") (pinfunction "3_3") (pintype "passive"))
      (node (ref "B3") (pin "3") (pinfunction "3_3") (pintype "passive"))
      (node (ref "B4") (pin "3") (pinfunction "3_3") (pintype "passive"))
      (node (ref "B5") (pin "3") (pinfunction "3_3") (pintype "passive"))
      (node (ref "B6") (pin "3") (pinfunction "3_3") (pintype "passive"))
      (node (ref "B7") (pin "3") (pinfunction "3_3") (pintype "passive"))
      (node (ref "B8") (pin "3") (pinfunction "3_3") (pintype "passive"))
      (node (ref "B9") (pin "3") (pinfunction "3_3") (pintype "passive"))
      (node (ref "LS1") (pin "1") (pinfunction "1_1") (pintype "passive"))
      (node (ref "LS11") (pin "1") (pinfunction "1_1") (pintype "passive"))
      (node (ref "LS13") (pin "1") (pinfunction "1_1") (pintype "passive"))
      (node (ref "LS15") (pin "1") (pinfunction "1_1") (pintype "passive"))
      (node (ref "LS17") (pin "1") (pinfunction "1_1") (pintype "passive"))
      (node (ref "LS19") (pin "1") (pinfunction "1_1") (pintype "passive"))
      (node (ref "LS21") (pin "1") (pinfunction "1_1") (pintype "passive"))
      (node (ref "LS23") (pin "1") (pinfunction "1_1") (pintype "passive"))
      (node (ref "LS3") (pin "1") (pinfunction "1_1") (pintype "passive"))
      (node (ref "LS5") (pin "1") (pinfunction "1_1") (pintype "passive"))
      (node (ref "LS7") (pin "1") (pinfunction "1_1") (pintype "passive"))
      (node (ref "LS9") (pin "1") (pinfunction "1_1") (pintype "passive"))
      (node (ref "P23") (pin "1") (pinfunction "1_1") (pintype "passive"))
      (node (ref "U9") (pin "1") (pinfunction "+OUT_L_1") (pintype "passive"))
    )
    (net (code "17") (name "/TR1-") (class "Default")
      (node (ref "B1") (pin "4") (pinfunction "4_4") (pintype "passive"))
      (node (ref "B10") (pin "4") (pinfunction "4_4") (pintype "passive"))
      (node (ref "B11") (pin "4") (pinfunction "4_4") (pintype "passive"))
      (node (ref "B2") (pin "4") (pinfunction "4_4") (pintype "passive"))
      (node (ref "B3") (pin "4") (pinfunction "4_4") (pintype "passive"))
      (node (ref "B4") (pin "4") (pinfunction "4_4") (pintype "passive"))
      (node (ref "B5") (pin "4") (pinfunction "4_4") (pintype "passive"))
      (node (ref "B6") (pin "4") (pinfunction "4_4") (pintype "passive"))
      (node (ref "B7") (pin "4") (pinfunction "4_4") (pintype "passive"))
      (node (ref "B8") (pin "4") (pinfunction "4_4") (pintype "passive"))
      (node (ref "B9") (pin "4") (pinfunction "4_4") (pintype "passive"))
      (node (ref "LS1") (pin "2") (pinfunction "2_2") (pintype "passive"))
      (node (ref "LS11") (pin "2") (pinfunction "2_2") (pintype "passive"))
      (node (ref "LS13") (pin "2") (pinfunction "2_2") (pintype "passive"))
      (node (ref "LS15") (pin "2") (pinfunction "2_2") (pintype "passive"))
      (node (ref "LS17") (pin "2") (pinfunction "2_2") (pintype "passive"))
      (node (ref "LS19") (pin "2") (pinfunction "2_2") (pintype "passive"))
      (node (ref "LS21") (pin "2") (pinfunction "2_2") (pintype "passive"))
      (node (ref "LS23") (pin "2") (pinfunction "2_2") (pintype "passive"))
      (node (ref "LS3") (pin "2") (pinfunction "2_2") (pintype "passive"))
      (node (ref "LS5") (pin "2") (pinfunction "2_2") (pintype "passive"))
      (node (ref "LS7") (pin "2") (pinfunction "2_2") (pintype "passive"))
      (node (ref "LS9") (pin "2") (pinfunction "2_2") (pintype "passive"))
      (node (ref "P23") (pin "2") (pinfunction "2_2") (pintype "passive"))
      (node (ref "U9") (pin "3") (pinfunction "-OUT_L_3") (pintype "passive"))
    )
    (net (code "18") (name "/TR2+") (class "Default")
      (node (ref "B1") (pin "1") (pinfunction "1_1") (pintype "passive"))
      (node (ref "B10") (pin "1") (pinfunction "1_1") (pintype "passive"))
      (node (ref "B11") (pin "1") (pinfunction "1_1") (pintype "passive"))
      (node (ref "B2") (pin "1") (pinfunction "1_1") (pintype "passive"))
      (node (ref "B3") (pin "1") (pinfunction "1_1") (pintype "passive"))
      (node (ref "B4") (pin "1") (pinfunction "1_1") (pintype "passive"))
      (node (ref "B5") (pin "1") (pinfunction "1_1") (pintype "passive"))
      (node (ref "B6") (pin "1") (pinfunction "1_1") (pintype "passive"))
      (node (ref "B7") (pin "1") (pinfunction "1_1") (pintype "passive"))
      (node (ref "B8") (pin "1") (pinfunction "1_1") (pintype "passive"))
      (node (ref "B9") (pin "1") (pinfunction "1_1") (pintype "passive"))
      (node (ref "LS10") (pin "1") (pinfunction "1_1") (pintype "passive"))
      (node (ref "LS12") (pin "1") (pinfunction "1_1") (pintype "passive"))
      (node (ref "LS14") (pin "1") (pinfunction "1_1") (pintype "passive"))
      (node (ref "LS16") (pin "1") (pinfunction "1_1") (pintype "passive"))
      (node (ref "LS18") (pin "1") (pinfunction "1_1") (pintype "passive"))
      (node (ref "LS2") (pin "1") (pinfunction "1_1") (pintype "passive"))
      (node (ref "LS20") (pin "1") (pinfunction "1_1") (pintype "passive"))
      (node (ref "LS22") (pin "1") (pinfunction "1_1") (pintype "passive"))
      (node (ref "LS24") (pin "1") (pinfunction "1_1") (pintype "passive"))
      (node (ref "LS4") (pin "1") (pinfunction "1_1") (pintype "passive"))
      (node (ref "LS6") (pin "1") (pinfunction "1_1") (pintype "passive"))
      (node (ref "LS8") (pin "1") (pinfunction "1_1") (pintype "passive"))
      (node (ref "P24") (pin "1") (pinfunction "1_1") (pintype "passive"))
      (node (ref "U9") (pin "16") (pinfunction "+OUT_R_16") (pintype "passive"))
    )
    (net (code "19") (name "/TR2-") (class "Default")
      (node (ref "B1") (pin "2") (pinfunction "2_2") (pintype "passive"))
      (node (ref "B10") (pin "2") (pinfunction "2_2") (pintype "passive"))
      (node (ref "B11") (pin "2") (pinfunction "2_2") (pintype "passive"))
      (node (ref "B2") (pin "2") (pinfunction "2_2") (pintype "passive"))
      (node (ref "B3") (pin "2") (pinfunction "2_2") (pintype "passive"))
      (node (ref "B4") (pin "2") (pinfunction "2_2") (pintype "passive"))
      (node (ref "B5") (pin "2") (pinfunction "2_2") (pintype "passive"))
      (node (ref "B6") (pin "2") (pinfunction "2_2") (pintype "passive"))
      (node (ref "B7") (pin "2") (pinfunction "2_2") (pintype "passive"))
      (node (ref "B8") (pin "2") (pinfunction "2_2") (pintype "passive"))
      (node (ref "B9") (pin "2") (pinfunction "2_2") (pintype "passive"))
      (node (ref "LS10") (pin "2") (pinfunction "2_2") (pintype "passive"))
      (node (ref "LS12") (pin "2") (pinfunction "2_2") (pintype "passive"))
      (node (ref "LS14") (pin "2") (pinfunction "2_2") (pintype "passive"))
      (node (ref "LS16") (pin "2") (pinfunction "2_2") (pintype "passive"))
      (node (ref "LS18") (pin "2") (pinfunction "2_2") (pintype "passive"))
      (node (ref "LS2") (pin "2") (pinfunction "2_2") (pintype "passive"))
      (node (ref "LS20") (pin "2") (pinfunction "2_2") (pintype "passive"))
      (node (ref "LS22") (pin "2") (pinfunction "2_2") (pintype "passive"))
      (node (ref "LS24") (pin "2") (pinfunction "2_2") (pintype "passive"))
      (node (ref "LS4") (pin "2") (pinfunction "2_2") (pintype "passive"))
      (node (ref "LS6") (pin "2") (pinfunction "2_2") (pintype "passive"))
      (node (ref "LS8") (pin "2") (pinfunction "2_2") (pintype "passive"))
      (node (ref "P24") (pin "2") (pinfunction "2_2") (pintype "passive"))
      (node (ref "U9") (pin "14") (pinfunction "-OUT_R_14") (pintype "passive"))
    )
    (net (code "20") (name "/TXD1_16u2") (class "Default")
      (node (ref "B1") (pin "7") (pinfunction "7_7") (pintype "passive"))
      (node (ref "B2") (pin "7") (pinfunction "7_7") (pintype "passive"))
      (node (ref "R37") (pin "2") (pinfunction "2_2") (pintype "passive"))
      (node (ref "U5") (pin "30") (pinfunction "RXD_30") (pintype "passive"))
    )
    (net (code "21") (name "/WAV_OUT") (class "Default")
      (node (ref "C14") (pin "2") (pinfunction "2_2") (pintype "passive"))
      (node (ref "C27") (pin "2") (pinfunction "2_2") (pintype "passive"))
      (node (ref "SB1") (pin "2") (pinfunction "1_2") (pintype "passive"))
      (node (ref "U8") (pin "10") (pinfunction "VOUT_10") (pintype "passive"))
    )
    (net (code "22") (name "/WAV_OUT_R") (class "Default")
      (node (ref "C28") (pin "2") (pinfunction "2_2") (pintype "passive"))
      (node (ref "SB1") (pin "1") (pinfunction "0_1") (pintype "passive"))
    )
    (net (code "23") (name "BAT5V") (class "Default")
      (node (ref "Q4") (pin "2") (pinfunction "S_2") (pintype "passive"))
    )
    (net (code "24") (name "GND") (class "Default")
      (node (ref "B1") (pin "5") (pinfunction "5_5") (pintype "passive"))
      (node (ref "B10") (pin "5") (pinfunction "5_5") (pintype "passive"))
      (node (ref "B11") (pin "5") (pinfunction "5_5") (pintype "passive"))
      (node (ref "B2") (pin "5") (pinfunction "5_5") (pintype "passive"))
      (node (ref "B3") (pin "5") (pinfunction "5_5") (pintype "passive"))
      (node (ref "B4") (pin "5") (pinfunction "5_5") (pintype "passive"))
      (node (ref "B5") (pin "5") (pinfunction "5_5") (pintype "passive"))
      (node (ref "B6") (pin "5") (pinfunction "5_5") (pintype "passive"))
      (node (ref "B7") (pin "5") (pinfunction "5_5") (pintype "passive"))
      (node (ref "B8") (pin "5") (pinfunction "5_5") (pintype "passive"))
      (node (ref "B9") (pin "5") (pinfunction "5_5") (pintype "passive"))
      (node (ref "C14") (pin "1") (pinfunction "1_1") (pintype "passive"))
      (node (ref "C15") (pin "1") (pinfunction "1_1") (pintype "passive"))
      (node (ref "C17") (pin "2") (pinfunction "2_2") (pintype "passive"))
      (node (ref "C19") (pin "1") (pinfunction "1_1") (pintype "passive"))
      (node (ref "C20") (pin "1") (pinfunction "1_1") (pintype "passive"))
      (node (ref "C21") (pin "2") (pinfunction "2_2") (pintype "passive"))
      (node (ref "C22") (pin "2") (pinfunction "2_2") (pintype "passive"))
      (node (ref "C23") (pin "2") (pinfunction "2_2") (pintype "passive"))
      (node (ref "C24") (pin "2") (pinfunction "2_2") (pintype "passive"))
      (node (ref "C25") (pin "2") (pinfunction "2_2") (pintype "passive"))
      (node (ref "C26") (pin "2") (pinfunction "2_2") (pintype "passive"))
      (node (ref "C29") (pin "2") (pinfunction "2_2") (pintype "passive"))
      (node (ref "C34") (pin "1") (pinfunction "1_1") (pintype "passive"))
      (node (ref "C35") (pin "1") (pinfunction "1_1") (pintype "passive"))
      (node (ref "C37") (pin "2") (pinfunction "2_2") (pintype "passive"))
      (node (ref "C38") (pin "2") (pinfunction "2_2") (pintype "passive"))
      (node (ref "C39") (pin "1") (pinfunction "1_1") (pintype "passive"))
      (node (ref "C41") (pin "1") (pinfunction "1_1") (pintype "passive"))
      (node (ref "C42") (pin "1") (pinfunction "1_1") (pintype "passive"))
      (node (ref "C43") (pin "2") (pinfunction "2_2") (pintype "passive"))
      (node (ref "C44") (pin "2") (pinfunction "2_2") (pintype "passive"))
      (node (ref "P22") (pin "1") (pinfunction "1_1") (pintype "passive"))
      (node (ref "P25") (pin "6") (pinfunction "6_6") (pintype "passive"))
      (node (ref "P26") (pin "6") (pinfunction "6_6") (pintype "passive"))
      (node (ref "R24") (pin "2") (pinfunction "2_2") (pintype "passive"))
      (node (ref "R33") (pin "1") (pinfunction "1_1") (pintype "passive"))
      (node (ref "R36") (pin "1") (pinfunction "1_1") (pintype "passive"))
      (node (ref "SB3") (pin "2") (pinfunction "1_2") (pintype "passive"))
      (node (ref "SW1") (pin "3") (pinfunction "S_3") (pintype "passive"))
      (node (ref "U11") (pin "3") (pinfunction "GND_3") (pintype "passive"))
      (node (ref "U11") (pin "33") (pinfunction "EXP_33") (pintype "passive"))
      (node (ref "U5") (pin "21") (pinfunction "GND_21") (pintype "passive"))
      (node (ref "U5") (pin "3") (pinfunction "GND_3") (pintype "passive"))
      (node (ref "U5") (pin "5") (pinfunction "GND_5") (pintype "passive"))
      (node (ref "U7") (pin "2") (pinfunction "VSS_2") (pintype "power_in"))
      (node (ref "U8") (pin "4") (pinfunction "DGND_4") (pintype "passive"))
      (node (ref "U8") (pin "9") (pinfunction "AGND_9") (pintype "passive"))
      (node (ref "U9") (pin "11") (pinfunction "GND_11") (pintype "passive"))
      (node (ref "U9") (pin "15") (pinfunction "PGND_2_15") (pintype "passive"))
      (node (ref "U9") (pin "2") (pinfunction "PGND_1_2") (pintype "passive"))
      (node (ref "U9") (pin "9") (pinfunction "NC_9") (pintype "passive"))
      (node (ref "Y1") (pin "2") (pinfunction "VSS_2") (pintype "passive"))
      (node (ref "Y3") (pin "2") (pinfunction "2_2") (pintype "passive"))
      (node (ref "Y3") (pin "4") (pinfunction "4_4") (pintype "passive"))
      (node (ref "Y4") (pin "2") (pinfunction "2_2") (pintype "passive"))
      (node (ref "Y4") (pin "4") (pinfunction "4_4") (pintype "passive"))
    )
    (net (code "25") (name "Net-(C27-Pad1)") (class "Default")
      (node (ref "C27") (pin "1") (pinfunction "1_1") (pintype "passive"))
      (node (ref "R29") (pin "2") (pinfunction "2_2") (pintype "passive"))
    )
    (net (code "26") (name "Net-(C28-Pad1)") (class "Default")
      (node (ref "C28") (pin "1") (pinfunction "1_1") (pintype "passive"))
      (node (ref "R30") (pin "2") (pinfunction "2_2") (pintype "passive"))
    )
    (net (code "27") (name "Net-(D4-A)") (class "Default")
      (node (ref "D4") (pin "1") (pinfunction "A_1") (pintype "passive"))
      (node (ref "Q1") (pin "2") (pinfunction "S_2") (pintype "passive"))
      (node (ref "Q4") (pin "3") (pinfunction "D_3") (pintype "passive"))
      (node (ref "R2") (pin "1") (pinfunction "1_1") (pintype "passive"))
    )
    (net (code "28") (name "Net-(J1-D+)") (class "Default")
      (node (ref "J1") (pin "3") (pinfunction "D+_3") (pintype "passive"))
      (node (ref "R27") (pin "2") (pinfunction "2_2") (pintype "passive"))
    )
    (net (code "29") (name "Net-(J1-D-)") (class "Default")
      (node (ref "J1") (pin "2") (pinfunction "D-_2") (pintype "passive"))
      (node (ref "R26") (pin "2") (pinfunction "2_2") (pintype "passive"))
    )
    (net (code "30") (name "Net-(J1-V_BUS_(5V))") (class "Default")
      (node (ref "J1") (pin "1") (pinfunction "V_BUS_(5V)_1") (pintype "passive"))
      (node (ref "L1") (pin "1") (pinfunction "1_1") (pintype "passive"))
    )
    (net (code "31") (name "Net-(L3-Pad2)") (class "Default")
      (node (ref "L3") (pin "2") (pinfunction "2_2") (pintype "passive"))
      (node (ref "Z3") (pin "1") (pinfunction "1_1") (pintype "passive"))
      (node (ref "Z4") (pin "1") (pinfunction "1_1") (pintype "passive"))
    )
    (net (code "32") (name "Net-(LED1-PadA)") (class "Default")
      (node (ref "LED1") (pin "A") (pinfunction "A_A") (pintype "passive"))
      (node (ref "R25") (pin "1") (pinfunction "1_1") (pintype "passive"))
    )
    (net (code "33") (name "Net-(Q1-G)") (class "Default")
      (node (ref "Q1") (pin "1") (pinfunction "G_1") (pintype "passive"))
      (node (ref "R2") (pin "2") (pinfunction "2_2") (pintype "passive"))
      (node (ref "R7") (pin "1") (pinfunction "1_1") (pintype "passive"))
    )
    (net (code "34") (name "Net-(SW1A-P)") (class "Default")
      (node (ref "R7") (pin "2") (pinfunction "2_2") (pintype "passive"))
      (node (ref "SW1") (pin "2") (pinfunction "P_2") (pintype "passive"))
    )
    (net (code "35") (name "Net-(U5-AD1)") (class "Default")
      (node (ref "TP9") (pin "1") (pintype "passive"))
      (node (ref "U5") (pin "24") (pinfunction "AD1_24") (pintype "passive"))
    )
    (net (code "36") (name "Net-(U5-XTAL1)") (class "Default")
      (node (ref "C43") (pin "1") (pinfunction "1_1") (pintype "passive"))
      (node (ref "U5") (pin "7") (pinfunction "XTAL1_7") (pintype "passive"))
      (node (ref "Y4") (pin "1") (pinfunction "1_1") (pintype "passive"))
    )
    (net (code "37") (name "Net-(U5-XTAL2)") (class "Default")
      (node (ref "C44") (pin "1") (pinfunction "1_1") (pintype "passive"))
      (node (ref "U5") (pin "8") (pinfunction "XTAL2_8") (pintype "passive"))
      (node (ref "Y4") (pin "3") (pinfunction "3_3") (pintype "passive"))
    )
    (net (code "38") (name "Net-(U7-PROG)") (class "Default")
      (node (ref "R24") (pin "1") (pinfunction "1_1") (pintype "passive"))
      (node (ref "U7") (pin "5") (pinfunction "PROG_5") (pintype "passive"))
    )
    (net (code "39") (name "Net-(U7-STAT)") (class "Default")
      (node (ref "LED1") (pin "C") (pinfunction "C_C") (pintype "passive"))
      (node (ref "U7") (pin "1") (pinfunction "STAT_1") (pintype "output"))
    )
    (net (code "40") (name "Net-(U8-CAP{slash}2.5V)") (class "Default")
      (node (ref "C20") (pin "2") (pinfunction "2_2") (pintype "passive"))
      (node (ref "C21") (pin "1") (pinfunction "1_1") (pintype "passive"))
      (node (ref "U8") (pin "3") (pinfunction "CAP/2.5V_3") (pintype "passive"))
    )
    (net (code "41") (name "Net-(U8-COMP)") (class "Default")
      (node (ref "C18") (pin "2") (pinfunction "2_2") (pintype "passive"))
      (node (ref "U8") (pin "1") (pinfunction "COMP_1") (pintype "passive"))
    )
    (net (code "42") (name "Net-(U8-FSYNC)") (class "Default")
      (node (ref "R21") (pin "2") (pinfunction "2_2") (pintype "passive"))
      (node (ref "U8") (pin "8") (pinfunction "FSYNC_8") (pintype "passive"))
    )
    (net (code "43") (name "Net-(U8-MCLK)") (class "Default")
      (node (ref "U8") (pin "5") (pinfunction "MCLK_5") (pintype "passive"))
      (node (ref "Y1") (pin "3") (pinfunction "CLK_3") (pintype "passive"))
    )
    (net (code "44") (name "Net-(U8-SCLK)") (class "Default")
      (node (ref "R22") (pin "2") (pinfunction "2_2") (pintype "passive"))
      (node (ref "U8") (pin "7") (pinfunction "SCLK_7") (pintype "passive"))
    )
    (net (code "45") (name "Net-(U8-SDATA)") (class "Default")
      (node (ref "R23") (pin "2") (pinfunction "2_2") (pintype "passive"))
      (node (ref "U8") (pin "6") (pinfunction "SDATA_6") (pintype "passive"))
    )
    (net (code "46") (name "Net-(U9-INL)") (class "Default")
      (node (ref "R29") (pin "1") (pinfunction "1_1") (pintype "passive"))
      (node (ref "U9") (pin "7") (pinfunction "INL_7") (pintype "passive"))
    )
    (net (code "47") (name "Net-(U9-INR)") (class "Default")
      (node (ref "R30") (pin "1") (pinfunction "1_1") (pintype "passive"))
      (node (ref "U9") (pin "10") (pinfunction "INR_10") (pintype "passive"))
    )
    (net (code "48") (name "Net-(U9-VREF)") (class "Default")
      (node (ref "C29") (pin "1") (pinfunction "1_1") (pintype "passive"))
      (node (ref "U9") (pin "8") (pinfunction "VREF_8") (pintype "passive"))
    )
    (net (code "49") (name "Net-(U11-PC0)") (class "Default")
      (node (ref "C37") (pin "1") (pinfunction "1_1") (pintype "passive"))
      (node (ref "U11") (pin "2") (pinfunction "PC0_2") (pintype "passive"))
      (node (ref "Y3") (pin "1") (pinfunction "1_1") (pintype "passive"))
    )
    (net (code "50") (name "Net-(U11-PD2)") (class "Default")
      (node (ref "R38") (pin "1") (pinfunction "1_1") (pintype "passive"))
      (node (ref "U11") (pin "8") (pinfunction "PD2_8") (pintype "passive"))
    )
    (net (code "51") (name "Net-(U11-PD3)") (class "Default")
      (node (ref "R37") (pin "1") (pinfunction "1_1") (pintype "passive"))
      (node (ref "U11") (pin "9") (pinfunction "PD3_9") (pintype "passive"))
    )
    (net (code "52") (name "Net-(U11-UCAP)") (class "Default")
      (node (ref "C40") (pin "2") (pinfunction "2_2") (pintype "passive"))
      (node (ref "U11") (pin "27") (pinfunction "UCAP_27") (pintype "passive"))
    )
    (net (code "53") (name "Net-(U11-XTAL1)") (class "Default")
      (node (ref "C38") (pin "1") (pinfunction "1_1") (pintype "passive"))
      (node (ref "U11") (pin "1") (pinfunction "XTAL1_1") (pintype "passive"))
      (node (ref "Y3") (pin "3") (pinfunction "3_3") (pintype "passive"))
    )
    (net (code "54") (name "Net-(Y1-STBY)") (class "Default")
      (node (ref "C26") (pin "1") (pinfunction "1_1") (pintype "passive"))
      (node (ref "R28") (pin "2") (pinfunction "2_2") (pintype "passive"))
      (node (ref "Y1") (pin "1") (pinfunction "STBY_1") (pintype "passive"))
      (node (ref "Y1") (pin "4") (pinfunction "VDD_4") (pintype "passive"))
    )
    (net (code "55") (name "UGND") (class "Default")
      (node (ref "C16") (pin "1") (pinfunction "1_1") (pintype "passive"))
      (node (ref "C40") (pin "1") (pinfunction "1_1") (pintype "passive"))
      (node (ref "J1") (pin "5") (pinfunction "GND_5") (pintype "passive"))
      (node (ref "J1") (pin "MH1") (pinfunction "Tab_MH1") (pintype "passive"))
      (node (ref "J1") (pin "MH2") (pinfunction "Tab_MH2") (pintype "passive"))
      (node (ref "J1") (pin "MH3") (pinfunction "Tab_MH3") (pintype "passive"))
      (node (ref "J1") (pin "MH4") (pinfunction "Tab_MH4") (pintype "passive"))
      (node (ref "L3") (pin "1") (pinfunction "1_1") (pintype "passive"))
      (node (ref "SB3") (pin "1") (pinfunction "0_1") (pintype "passive"))
      (node (ref "U11") (pin "28") (pinfunction "UGND_28") (pintype "passive"))
    )
    (net (code "56") (name "VBAT") (class "Default")
      (node (ref "C19") (pin "2") (pinfunction "2_2") (pintype "passive"))
      (node (ref "P22") (pin "2") (pinfunction "2_2") (pintype "passive"))
      (node (ref "U7") (pin "3") (pinfunction "VBAT_3") (pintype "power_in"))
    )
    (net (code "57") (name "VBUS") (class "Default")
      (node (ref "C16") (pin "2") (pinfunction "2_2") (pintype "passive"))
      (node (ref "C35") (pin "2") (pinfunction "2_2") (pintype "passive"))
      (node (ref "D4") (pin "2") (pinfunction "K_2") (pintype "passive"))
      (node (ref "L1") (pin "2") (pinfunction "2_2") (pintype "passive"))
      (node (ref "Q4") (pin "1") (pinfunction "G_1") (pintype "passive"))
      (node (ref "R25") (pin "2") (pinfunction "2_2") (pintype "passive"))
      (node (ref "R33") (pin "2") (pinfunction "2_2") (pintype "passive"))
      (node (ref "U11") (pin "31") (pinfunction "UVCC_31") (pintype "passive"))
      (node (ref "U7") (pin "4") (pinfunction "VDD_4") (pintype "power_in"))
    )
    (net (code "58") (name "VCC5V") (class "Default")
      (node (ref "B1") (pin "9") (pinfunction "9_9") (pintype "passive"))
      (node (ref "B2") (pin "9") (pinfunction "9_9") (pintype "passive"))
      (node (ref "C15") (pin "2") (pinfunction "2_2") (pintype "passive"))
      (node (ref "C17") (pin "1") (pinfunction "1_1") (pintype "passive"))
      (node (ref "C18") (pin "1") (pinfunction "1_1") (pintype "passive"))
      (node (ref "C22") (pin "1") (pinfunction "1_1") (pintype "passive"))
      (node (ref "C23") (pin "1") (pinfunction "1_1") (pintype "passive"))
      (node (ref "C24") (pin "1") (pinfunction "1_1") (pintype "passive"))
      (node (ref "C25") (pin "1") (pinfunction "1_1") (pintype "passive"))
      (node (ref "C34") (pin "2") (pinfunction "2_2") (pintype "passive"))
      (node (ref "C39") (pin "2") (pinfunction "2_2") (pintype "passive"))
      (node (ref "C41") (pin "2") (pinfunction "2_2") (pintype "passive"))
      (node (ref "C42") (pin "2") (pinfunction "2_2") (pintype "passive"))
      (node (ref "D5") (pin "2") (pinfunction "K_2") (pintype "passive"))
      (node (ref "D6") (pin "2") (pinfunction "K_2") (pintype "passive"))
      (node (ref "P25") (pin "2") (pinfunction "2_2") (pintype "passive"))
      (node (ref "P26") (pin "2") (pinfunction "2_2") (pintype "passive"))
      (node (ref "Q1") (pin "3") (pinfunction "D_3") (pintype "passive"))
      (node (ref "R28") (pin "1") (pinfunction "1_1") (pintype "passive"))
      (node (ref "R34") (pin "2") (pinfunction "2_2") (pintype "passive"))
      (node (ref "R35") (pin "2") (pinfunction "2_2") (pintype "passive"))
      (node (ref "U11") (pin "32") (pinfunction "AVCC_32") (pintype "passive"))
      (node (ref "U11") (pin "4") (pinfunction "VCC_4") (pintype "passive"))
      (node (ref "U5") (pin "18") (pinfunction "AVCC_18") (pintype "passive"))
      (node (ref "U5") (pin "20") (pinfunction "AREF_20") (pintype "passive"))
      (node (ref "U5") (pin "4") (pinfunction "VCC_4") (pintype "passive"))
      (node (ref "U5") (pin "6") (pinfunction "VCC_6") (pintype "passive"))
      (node (ref "U8") (pin "2") (pinfunction "VDD_2") (pintype "passive"))
      (node (ref "U9") (pin "12") (pinfunction "SHND_12") (pintype "passive"))
      (node (ref "U9") (pin "13") (pinfunction "PVDD_2_13") (pintype "passive"))
      (node (ref "U9") (pin "4") (pinfunction "PVDD_1_4") (pintype "passive"))
      (node (ref "U9") (pin "5") (pinfunction "MUTE_5") (pintype "passive"))
      (node (ref "U9") (pin "6") (pinfunction "VDD_6") (pintype "passive"))
    )
    (net (code "59") (name "unconnected-(B3-Pad6)") (class "Default")
      (node (ref "B3") (pin "6") (pinfunction "6_6") (pintype "passive"))
    )
    (net (code "60") (name "unconnected-(B4-Pad6)") (class "Default")
      (node (ref "B4") (pin "6") (pinfunction "6_6") (pintype "passive"))
    )
    (net (code "61") (name "unconnected-(B5-Pad6)") (class "Default")
      (node (ref "B5") (pin "6") (pinfunction "6_6") (pintype "passive"))
    )
    (net (code "62") (name "unconnected-(B6-Pad6)") (class "Default")
      (node (ref "B6") (pin "6") (pinfunction "6_6") (pintype "passive"))
    )
    (net (code "63") (name "unconnected-(B7-Pad6)") (class "Default")
      (node (ref "B7") (pin "6") (pinfunction "6_6") (pintype "passive"))
    )
    (net (code "64") (name "unconnected-(B8-Pad6)") (class "Default")
      (node (ref "B8") (pin "6") (pinfunction "6_6") (pintype "passive"))
    )
    (net (code "65") (name "unconnected-(B9-Pad6)") (class "Default")
      (node (ref "B9") (pin "6") (pinfunction "6_6") (pintype "passive"))
    )
    (net (code "66") (name "unconnected-(B10-Pad6)") (class "Default")
      (node (ref "B10") (pin "6") (pinfunction "6_6") (pintype "passive"))
    )
    (net (code "67") (name "unconnected-(B11-Pad6)") (class "Default")
      (node (ref "B11") (pin "6") (pinfunction "6_6") (pintype "passive"))
    )
    (net (code "68") (name "unconnected-(J1-NC-Pad4)") (class "Default")
      (node (ref "J1") (pin "4") (pinfunction "NC_4") (pintype "passive"))
    )
    (net (code "69") (name "unconnected-(SW1A-O-Pad1)") (class "Default")
      (node (ref "SW1") (pin "1") (pinfunction "O_1") (pintype "passive"))
    )
    (net (code "70") (name "unconnected-(U5-ADC6-Pad19)") (class "Default")
      (node (ref "U5") (pin "19") (pinfunction "ADC6_19") (pintype "passive"))
    )
    (net (code "71") (name "unconnected-(U5-ADC7-Pad22)") (class "Default")
      (node (ref "U5") (pin "22") (pinfunction "ADC7_22") (pintype "passive"))
    )
    (net (code "72") (name "unconnected-(U5-PB0-Pad12)") (class "Default")
      (node (ref "U5") (pin "12") (pinfunction "PB0_12") (pintype "passive"))
    )
    (net (code "73") (name "unconnected-(U5-PB1-Pad13)") (class "Default")
      (node (ref "U5") (pin "13") (pinfunction "PB1_13") (pintype "passive"))
    )
    (net (code "74") (name "unconnected-(U5-PB2-Pad14)") (class "Default")
      (node (ref "U5") (pin "14") (pinfunction "PB2_14") (pintype "passive"))
    )
    (net (code "75") (name "unconnected-(U5-PC2-Pad25)") (class "Default")
      (node (ref "U5") (pin "25") (pinfunction "PC2_25") (pintype "passive"))
    )
    (net (code "76") (name "unconnected-(U5-PC3-Pad26)") (class "Default")
      (node (ref "U5") (pin "26") (pinfunction "PC3_26") (pintype "passive"))
    )
    (net (code "77") (name "unconnected-(U5-PC4-Pad27)") (class "Default")
      (node (ref "U5") (pin "27") (pinfunction "PC4_27") (pintype "passive"))
    )
    (net (code "78") (name "unconnected-(U5-PC5-Pad28)") (class "Default")
      (node (ref "U5") (pin "28") (pinfunction "PC5_28") (pintype "passive"))
    )
    (net (code "79") (name "unconnected-(U5-PD2-Pad32)") (class "Default")
      (node (ref "U5") (pin "32") (pinfunction "PD2_32") (pintype "passive"))
    )
    (net (code "80") (name "unconnected-(U5-PD3-Pad1)") (class "Default")
      (node (ref "U5") (pin "1") (pinfunction "PD3_1") (pintype "passive"))
    )
    (net (code "81") (name "unconnected-(U5-PD4-Pad2)") (class "Default")
      (node (ref "U5") (pin "2") (pinfunction "PD4_2") (pintype "passive"))
    )
    (net (code "82") (name "unconnected-(U5-PD5-Pad9)") (class "Default")
      (node (ref "U5") (pin "9") (pinfunction "PD5_9") (pintype "passive"))
    )
    (net (code "83") (name "unconnected-(U5-PD6-Pad10)") (class "Default")
      (node (ref "U5") (pin "10") (pinfunction "PD6_10") (pintype "passive"))
    )
    (net (code "84") (name "unconnected-(U5-PD7-Pad11)") (class "Default")
      (node (ref "U5") (pin "11") (pinfunction "PD7_11") (pintype "passive"))
    )
    (net (code "85") (name "unconnected-(U11-PB0-Pad14)") (class "Default")
      (node (ref "U11") (pin "14") (pinfunction "PB0_14") (pintype "passive"))
    )
    (net (code "86") (name "unconnected-(U11-PB4-Pad18)") (class "Default")
      (node (ref "U11") (pin "18") (pinfunction "PB4_18") (pintype "passive"))
    )
    (net (code "87") (name "unconnected-(U11-PB5-Pad19)") (class "Default")
      (node (ref "U11") (pin "19") (pinfunction "PB5_19") (pintype "passive"))
    )
    (net (code "88") (name "unconnected-(U11-PB6-Pad20)") (class "Default")
      (node (ref "U11") (pin "20") (pinfunction "PB6_20") (pintype "passive"))
    )
    (net (code "89") (name "unconnected-(U11-PB7-Pad21)") (class "Default")
      (node (ref "U11") (pin "21") (pinfunction "PB7_21") (pintype "passive"))
    )
    (net (code "90") (name "unconnected-(U11-PC2-Pad5)") (class "Default")
      (node (ref "U11") (pin "5") (pinfunction "PC2_5") (pintype "passive"))
    )
    (net (code "91") (name "unconnected-(U11-PC4-Pad26)") (class "Default")
      (node (ref "U11") (pin "26") (pinfunction "PC4_26") (pintype "passive"))
    )
    (net (code "92") (name "unconnected-(U11-PC5-Pad25)") (class "Default")
      (node (ref "U11") (pin "25") (pinfunction "PC5_25") (pintype "passive"))
    )
    (net (code "93") (name "unconnected-(U11-PC6-Pad23)") (class "Default")
      (node (ref "U11") (pin "23") (pinfunction "PC6_23") (pintype "passive"))
    )
    (net (code "94") (name "unconnected-(U11-PC7-Pad22)") (class "Default")
      (node (ref "U11") (pin "22") (pinfunction "PC7_22") (pintype "passive"))
    )
    (net (code "95") (name "unconnected-(U11-PD0-Pad6)") (class "Default")
      (node (ref "U11") (pin "6") (pinfunction "PD0_6") (pintype "passive"))
    )
    (net (code "96") (name "unconnected-(U11-PD1-Pad7)") (class "Default")
      (node (ref "U11") (pin "7") (pinfunction "PD1_7") (pintype "passive"))
    )
    (net (code "97") (name "unconnected-(U11-PD4-Pad10)") (class "Default")
      (node (ref "U11") (pin "10") (pinfunction "PD4_10") (pintype "passive"))
    )
    (net (code "98") (name "unconnected-(U11-PD5-Pad11)") (class "Default")
      (node (ref "U11") (pin "11") (pinfunction "PD5_11") (pintype "passive"))
    )
    (net (code "99") (name "unconnected-(U11-PD6-Pad12)") (class "Default")
      (node (ref "U11") (pin "12") (pinfunction "PD6_12") (pintype "passive"))
    )
  )
)
